# mySatellite.net
KiCad netlist of a schematic drawn in EAGLE
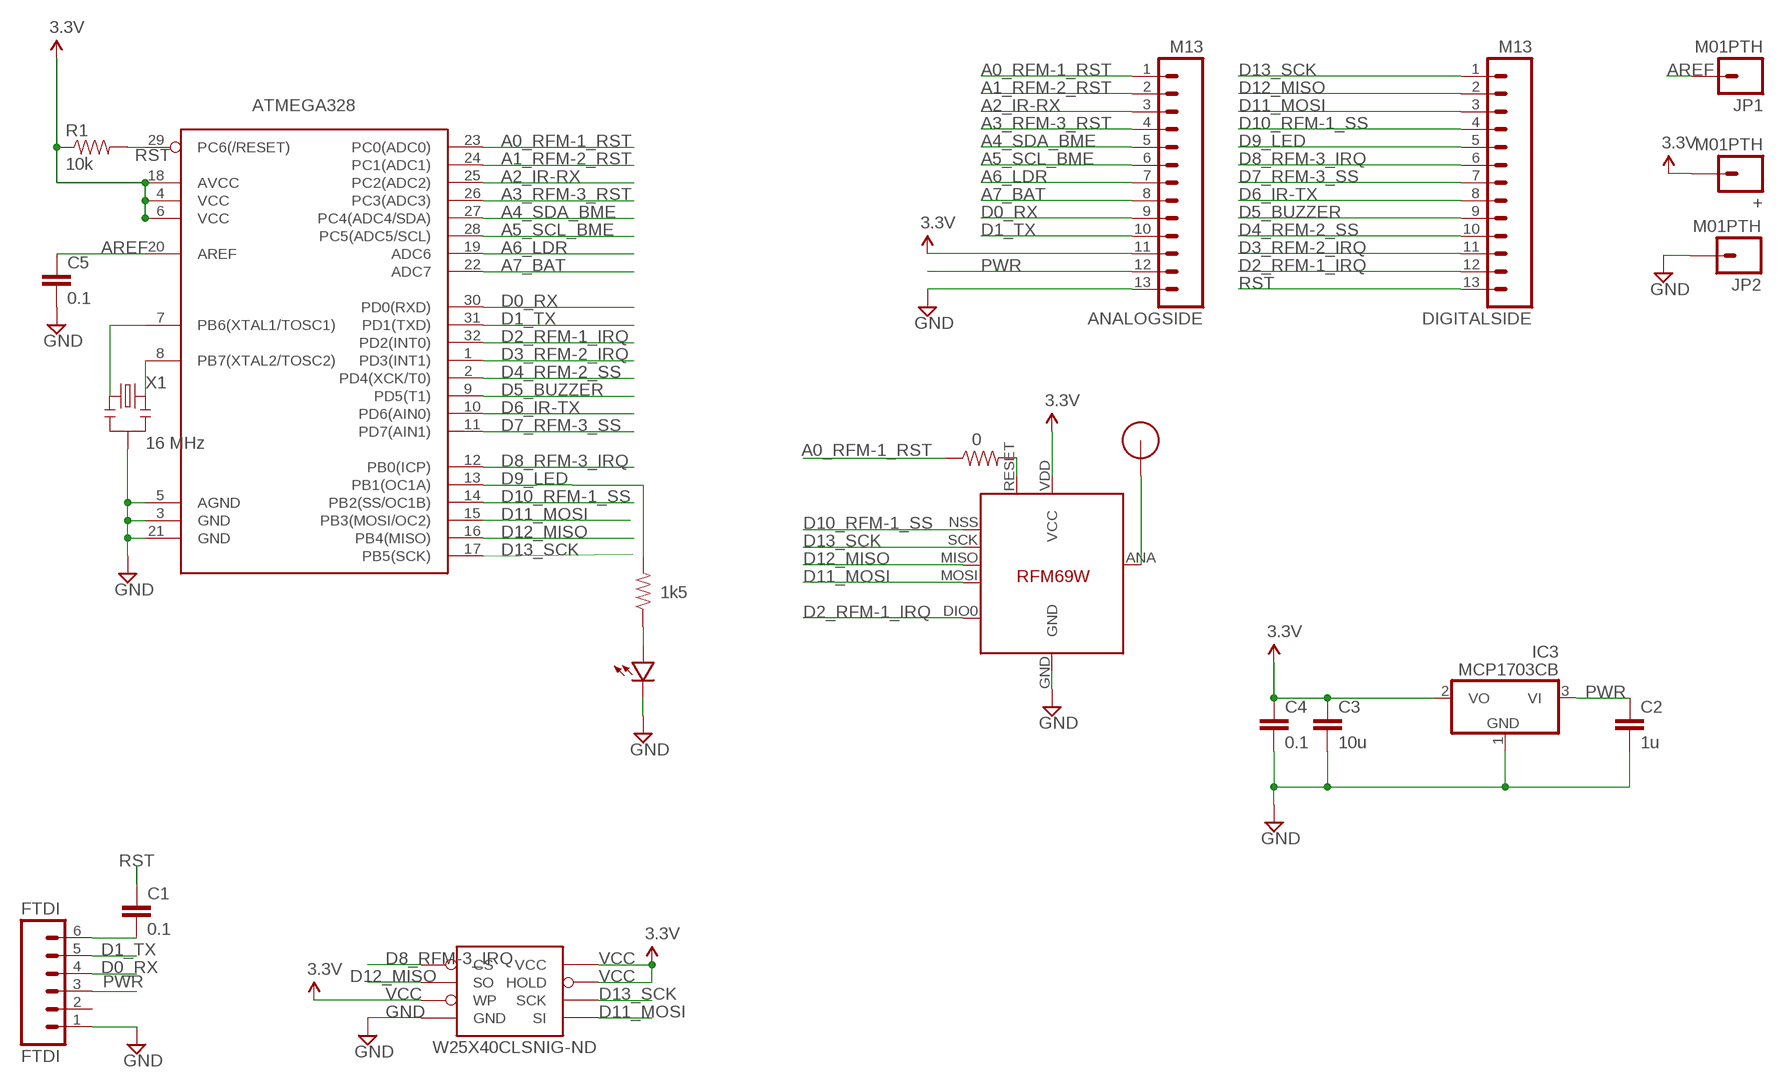
[diagram p0: schematic, sheet 1]

(export (version "E")
  (design (tool "Eeschema 10.0.6"))
  (components
    (comp (ref "+")
      (value "M01PTH")
      (footprint "eagle-import:1X01")
      (libsource (lib "eagle-import") (part "M01PTH"))
    )
    (comp (ref "ANALOGSIDE")
      (value "M13")
      (footprint "eagle-import:1X13")
      (libsource (lib "eagle-import") (part "M13"))
    )
    (comp (ref "ATMEGA328")
      (value "ATMega-328")
      (footprint "eagle-import:TQFP32-08")
      (libsource (lib "eagle-import") (part "ATMEGA168/328TQFP32"))
    )
    (comp (ref "C1")
      (value "0.1")
      (footprint "eagle-import:0603-CAP")
      (libsource (lib "eagle-import") (part "CAP0603-CAP"))
    )
    (comp (ref "C2")
      (value "1u")
      (footprint "eagle-import:0603-CAP")
      (libsource (lib "eagle-import") (part "CAP0603-CAP"))
    )
    (comp (ref "C3")
      (value "10u")
      (footprint "eagle-import:0805-CAP")
      (libsource (lib "eagle-import") (part "CAP0805-CAP"))
    )
    (comp (ref "C4")
      (value "0.1")
      (footprint "eagle-import:0603-CAP")
      (libsource (lib "eagle-import") (part "CAP0603-CAP"))
    )
    (comp (ref "C5")
      (value "0.1")
      (footprint "eagle-import:0603-CAP")
      (libsource (lib "eagle-import") (part "CAP0603-CAP"))
    )
    (comp (ref "DIGITALSIDE")
      (value "M13")
      (footprint "eagle-import:1X13")
      (libsource (lib "eagle-import") (part "M13"))
    )
    (comp (ref "FTDI")
      (value "FTDI")
      (footprint "eagle-import:1X06")
      (libsource (lib "eagle-import") (part "M06SIP"))
    )
    (comp (ref "IC3")
      (value "MCP1703CB")
      (footprint "eagle-import:SOT23")
      (libsource (lib "eagle-import") (part "MCP1703CB"))
    )
    (comp (ref "JP1")
      (value "M01PTH")
      (footprint "eagle-import:1X01")
      (libsource (lib "eagle-import") (part "M01PTH"))
    )
    (comp (ref "JP2")
      (value "M01PTH")
      (footprint "eagle-import:1X01")
      (libsource (lib "eagle-import") (part "M01PTH"))
    )
    (comp (ref "R1")
      (value "10k")
      (footprint "eagle-import:0603-RES")
      (libsource (lib "eagle-import") (part "RESISTOR0603-RES"))
    )
    (comp (ref "R2")
      (value "1k5")
      (footprint "eagle-import:0603-RES")
      (libsource (lib "eagle-import") (part "RESISTOR0603-RES"))
    )
    (comp (ref "R3")
      (value "0")
      (footprint "eagle-import:0603-RES")
      (libsource (lib "eagle-import") (part "RESISTOR0603-RES"))
    )
    (comp (ref "U$1")
      (value "RFM12B_ANTENNA")
      (footprint "eagle-import:RFM12B-ANTENNA")
      (libsource (lib "eagle-import") (part "RFM12B_ANTENNA"))
    )
    (comp (ref "U$2")
      (value "LED0603")
      (footprint "eagle-import:0603-LED")
      (libsource (lib "eagle-import") (part "LED0603"))
    )
    (comp (ref "U$5")
      (value "RFM69_MINIPADS")
      (footprint "eagle-import:RFM69W-MINPADS")
      (libsource (lib "eagle-import") (part "RFM69_MINIPADS"))
    )
    (comp (ref "W25X40CLSNIG-ND")
      (value "AT25F512BWIDE_5.3MM")
      (footprint "eagle-import:SO08WIDE")
      (libsource (lib "eagle-import") (part "AT25F512BWIDE_5.3MM"))
    )
    (comp (ref "X1")
      (value "16 MHz")
      (footprint "eagle-import:RESONATOR-SMD")
      (libsource (lib "eagle-import") (part "RESONATORSMD"))
    )
  )
  (nets
    (net (code "1") (name "/A0_RFM-1_RST") (class "Default")
      (node (ref "ANALOGSIDE") (pin "1") (pinfunction "1_1") (pintype "passive"))
      (node (ref "ATMEGA328") (pin "23") (pinfunction "PC0(ADC0)_23") (pintype "bidirectional"))
      (node (ref "R3") (pin "1") (pinfunction "1_1") (pintype "passive"))
    )
    (net (code "2") (name "/A1_RFM-2_RST") (class "Default")
      (node (ref "ANALOGSIDE") (pin "2") (pinfunction "2_2") (pintype "passive"))
      (node (ref "ATMEGA328") (pin "24") (pinfunction "PC1(ADC1)_24") (pintype "bidirectional"))
    )
    (net (code "3") (name "/A2_IR-RX") (class "Default")
      (node (ref "ANALOGSIDE") (pin "3") (pinfunction "3_3") (pintype "passive"))
      (node (ref "ATMEGA328") (pin "25") (pinfunction "PC2(ADC2)_25") (pintype "bidirectional"))
    )
    (net (code "4") (name "/A3_RFM-3_RST") (class "Default")
      (node (ref "ANALOGSIDE") (pin "4") (pinfunction "4_4") (pintype "passive"))
      (node (ref "ATMEGA328") (pin "26") (pinfunction "PC3(ADC3)_26") (pintype "bidirectional"))
    )
    (net (code "5") (name "/A4_SDA_BME") (class "Default")
      (node (ref "ANALOGSIDE") (pin "5") (pinfunction "5_5") (pintype "passive"))
      (node (ref "ATMEGA328") (pin "27") (pinfunction "PC4(ADC4/SDA)_27") (pintype "bidirectional"))
    )
    (net (code "6") (name "/A5_SCL_BME") (class "Default")
      (node (ref "ANALOGSIDE") (pin "6") (pinfunction "6_6") (pintype "passive"))
      (node (ref "ATMEGA328") (pin "28") (pinfunction "PC5(ADC5/SCL)_28") (pintype "bidirectional"))
    )
    (net (code "7") (name "/A6_LDR") (class "Default")
      (node (ref "ANALOGSIDE") (pin "7") (pinfunction "7_7") (pintype "passive"))
      (node (ref "ATMEGA328") (pin "19") (pinfunction "ADC6_19") (pintype "bidirectional"))
    )
    (net (code "8") (name "/A7_BAT") (class "Default")
      (node (ref "ANALOGSIDE") (pin "8") (pinfunction "8_8") (pintype "passive"))
      (node (ref "ATMEGA328") (pin "22") (pinfunction "ADC7_22") (pintype "bidirectional"))
    )
    (net (code "9") (name "/AREF") (class "Default")
      (node (ref "ATMEGA328") (pin "20") (pinfunction "AREF_20") (pintype "bidirectional"))
      (node (ref "C5") (pin "1") (pinfunction "1_1") (pintype "passive"))
      (node (ref "JP1") (pin "1") (pinfunction "1_1") (pintype "passive"))
    )
    (net (code "10") (name "/D0_RX") (class "Default")
      (node (ref "ANALOGSIDE") (pin "9") (pinfunction "9_9") (pintype "passive"))
      (node (ref "ATMEGA328") (pin "30") (pinfunction "PD0(RXD)_30") (pintype "bidirectional"))
      (node (ref "FTDI") (pin "4") (pinfunction "4_4") (pintype "passive"))
    )
    (net (code "11") (name "/D1_TX") (class "Default")
      (node (ref "ANALOGSIDE") (pin "10") (pinfunction "10_10") (pintype "passive"))
      (node (ref "ATMEGA328") (pin "31") (pinfunction "PD1(TXD)_31") (pintype "bidirectional"))
      (node (ref "FTDI") (pin "5") (pinfunction "5_5") (pintype "passive"))
    )
    (net (code "12") (name "/D2_RFM-1_IRQ") (class "Default")
      (node (ref "ATMEGA328") (pin "32") (pinfunction "PD2(INT0)_32") (pintype "bidirectional"))
      (node (ref "DIGITALSIDE") (pin "12") (pinfunction "12_12") (pintype "passive"))
      (node (ref "U$5") (pin "DIO0") (pinfunction "DIO0/IRQ_DIO0") (pintype "open_collector"))
    )
    (net (code "13") (name "/D3_RFM-2_IRQ") (class "Default")
      (node (ref "ATMEGA328") (pin "1") (pinfunction "PD3(INT1)_1") (pintype "bidirectional"))
      (node (ref "DIGITALSIDE") (pin "11") (pinfunction "11_11") (pintype "passive"))
    )
    (net (code "14") (name "/D4_RFM-2_SS") (class "Default")
      (node (ref "ATMEGA328") (pin "2") (pinfunction "PD4(XCK/T0)_2") (pintype "bidirectional"))
      (node (ref "DIGITALSIDE") (pin "10") (pinfunction "10_10") (pintype "passive"))
    )
    (net (code "15") (name "/D5_BUZZER") (class "Default")
      (node (ref "ATMEGA328") (pin "9") (pinfunction "PD5(T1)_9") (pintype "bidirectional"))
      (node (ref "DIGITALSIDE") (pin "9") (pinfunction "9_9") (pintype "passive"))
    )
    (net (code "16") (name "/D6_IR-TX") (class "Default")
      (node (ref "ATMEGA328") (pin "10") (pinfunction "PD6(AIN0)_10") (pintype "bidirectional"))
      (node (ref "DIGITALSIDE") (pin "8") (pinfunction "8_8") (pintype "passive"))
    )
    (net (code "17") (name "/D7_RFM-3_SS") (class "Default")
      (node (ref "ATMEGA328") (pin "11") (pinfunction "PD7(AIN1)_11") (pintype "bidirectional"))
      (node (ref "DIGITALSIDE") (pin "7") (pinfunction "7_7") (pintype "passive"))
    )
    (net (code "18") (name "/D8_RFM-3_IRQ") (class "Default")
      (node (ref "ATMEGA328") (pin "12") (pinfunction "PB0(ICP)_12") (pintype "bidirectional"))
      (node (ref "DIGITALSIDE") (pin "6") (pinfunction "6_6") (pintype "passive"))
      (node (ref "W25X40CLSNIG-ND") (pin "1") (pinfunction "CS_1") (pintype "bidirectional"))
    )
    (net (code "19") (name "/D9_LED") (class "Default")
      (node (ref "ATMEGA328") (pin "13") (pinfunction "PB1(OC1A)_13") (pintype "bidirectional"))
      (node (ref "DIGITALSIDE") (pin "5") (pinfunction "5_5") (pintype "passive"))
      (node (ref "R2") (pin "2") (pinfunction "2_2") (pintype "passive"))
    )
    (net (code "20") (name "/D10_RFM-1_SS") (class "Default")
      (node (ref "ATMEGA328") (pin "14") (pinfunction "PB2(SS/OC1B)_14") (pintype "bidirectional"))
      (node (ref "DIGITALSIDE") (pin "4") (pinfunction "4_4") (pintype "passive"))
      (node (ref "U$5") (pin "NSS") (pinfunction "SEL_NSS") (pintype "input"))
    )
    (net (code "21") (name "/D11_MOSI") (class "Default")
      (node (ref "ATMEGA328") (pin "15") (pinfunction "PB3(MOSI/OC2)_15") (pintype "bidirectional"))
      (node (ref "DIGITALSIDE") (pin "3") (pinfunction "3_3") (pintype "passive"))
      (node (ref "U$5") (pin "MOSI") (pinfunction "MOSI_MOSI") (pintype "output"))
      (node (ref "W25X40CLSNIG-ND") (pin "5") (pinfunction "SI_5") (pintype "bidirectional"))
    )
    (net (code "22") (name "/D12_MISO") (class "Default")
      (node (ref "ATMEGA328") (pin "16") (pinfunction "PB4(MISO)_16") (pintype "bidirectional"))
      (node (ref "DIGITALSIDE") (pin "2") (pinfunction "2_2") (pintype "passive"))
      (node (ref "U$5") (pin "MISO") (pinfunction "MISO_MISO") (pintype "input"))
      (node (ref "W25X40CLSNIG-ND") (pin "2") (pinfunction "SO_2") (pintype "bidirectional"))
    )
    (net (code "23") (name "/D13_SCK") (class "Default")
      (node (ref "ATMEGA328") (pin "17") (pinfunction "PB5(SCK)_17") (pintype "bidirectional"))
      (node (ref "DIGITALSIDE") (pin "1") (pinfunction "1_1") (pintype "passive"))
      (node (ref "U$5") (pin "SCK") (pinfunction "SCK_SCK") (pintype "input"))
      (node (ref "W25X40CLSNIG-ND") (pin "6") (pinfunction "SCK_6") (pintype "bidirectional"))
    )
    (net (code "24") (name "/PWR") (class "Default")
      (node (ref "ANALOGSIDE") (pin "12") (pinfunction "12_12") (pintype "passive"))
      (node (ref "C2") (pin "1") (pinfunction "1_1") (pintype "passive"))
      (node (ref "FTDI") (pin "3") (pinfunction "3_3") (pintype "passive"))
      (node (ref "IC3") (pin "3") (pinfunction "VI_3") (pintype "input"))
    )
    (net (code "25") (name "/RST") (class "Default")
      (node (ref "ATMEGA328") (pin "29") (pinfunction "PC6(/RESET)_29") (pintype "bidirectional"))
      (node (ref "C1") (pin "1") (pinfunction "1_1") (pintype "passive"))
      (node (ref "DIGITALSIDE") (pin "13") (pinfunction "13_13") (pintype "passive"))
      (node (ref "R1") (pin "2") (pinfunction "2_2") (pintype "passive"))
    )
    (net (code "26") (name "3.3V") (class "Default")
      (node (ref "+") (pin "1") (pinfunction "1_1") (pintype "passive"))
      (node (ref "ANALOGSIDE") (pin "11") (pinfunction "11_11") (pintype "passive"))
      (node (ref "ATMEGA328") (pin "18") (pinfunction "AVCC_18") (pintype "bidirectional"))
      (node (ref "ATMEGA328") (pin "4") (pinfunction "VCC_4") (pintype "bidirectional"))
      (node (ref "ATMEGA328") (pin "6") (pinfunction "VCC_6") (pintype "bidirectional"))
      (node (ref "C3") (pin "1") (pinfunction "1_1") (pintype "passive"))
      (node (ref "C4") (pin "1") (pinfunction "1_1") (pintype "passive"))
      (node (ref "IC3") (pin "2") (pinfunction "VO_2") (pintype "passive"))
      (node (ref "R1") (pin "1") (pinfunction "1_1") (pintype "passive"))
      (node (ref "U$5") (pin "VDD") (pinfunction "VCC_VDD") (pintype "power_in"))
      (node (ref "W25X40CLSNIG-ND") (pin "3") (pinfunction "WP_3") (pintype "bidirectional"))
      (node (ref "W25X40CLSNIG-ND") (pin "7") (pinfunction "HOLD_7") (pintype "bidirectional"))
      (node (ref "W25X40CLSNIG-ND") (pin "8") (pinfunction "VCC_8") (pintype "bidirectional"))
    )
    (net (code "27") (name "GND") (class "Default")
      (node (ref "ANALOGSIDE") (pin "13") (pinfunction "13_13") (pintype "passive"))
      (node (ref "ATMEGA328") (pin "21") (pinfunction "GND_21") (pintype "bidirectional"))
      (node (ref "ATMEGA328") (pin "3") (pinfunction "GND_3") (pintype "bidirectional"))
      (node (ref "ATMEGA328") (pin "5") (pinfunction "AGND_5") (pintype "bidirectional"))
      (node (ref "C2") (pin "2") (pinfunction "2_2") (pintype "passive"))
      (node (ref "C3") (pin "2") (pinfunction "2_2") (pintype "passive"))
      (node (ref "C4") (pin "2") (pinfunction "2_2") (pintype "passive"))
      (node (ref "C5") (pin "2") (pinfunction "2_2") (pintype "passive"))
      (node (ref "FTDI") (pin "1") (pinfunction "1_1") (pintype "passive"))
      (node (ref "IC3") (pin "1") (pinfunction "GND_1") (pintype "passive"))
      (node (ref "JP2") (pin "1") (pinfunction "1_1") (pintype "passive"))
      (node (ref "U$2") (pin "MINUS") (pinfunction "MINUS_MINUS") (pintype "passive"))
      (node (ref "U$5") (pin "GND") (pinfunction "GND_GND") (pintype "power_in"))
      (node (ref "W25X40CLSNIG-ND") (pin "4") (pinfunction "GND_4") (pintype "bidirectional"))
      (node (ref "X1") (pin "2") (pinfunction "2_2") (pintype "passive"))
    )
    (net (code "28") (name "Net-(ATMEGA328-PB6(XTAL1{slash}TOSC1))") (class "Default")
      (node (ref "ATMEGA328") (pin "7") (pinfunction "PB6(XTAL1/TOSC1)_7") (pintype "bidirectional"))
      (node (ref "X1") (pin "1") (pinfunction "1_1") (pintype "passive"))
    )
    (net (code "29") (name "Net-(ATMEGA328-PB7(XTAL2{slash}TOSC2))") (class "Default")
      (node (ref "ATMEGA328") (pin "8") (pinfunction "PB7(XTAL2/TOSC2)_8") (pintype "bidirectional"))
      (node (ref "X1") (pin "3") (pinfunction "3_3") (pintype "passive"))
    )
    (net (code "30") (name "Net-(C1-Pad2)") (class "Default")
      (node (ref "C1") (pin "2") (pinfunction "2_2") (pintype "passive"))
      (node (ref "FTDI") (pin "6") (pinfunction "6_6") (pintype "passive"))
    )
    (net (code "31") (name "Net-(R2-Pad1)") (class "Default")
      (node (ref "R2") (pin "1") (pinfunction "1_1") (pintype "passive"))
      (node (ref "U$2") (pin "PLUS") (pinfunction "PLUS_PLUS") (pintype "passive"))
    )
    (net (code "32") (name "Net-(R3-Pad2)") (class "Default")
      (node (ref "R3") (pin "2") (pinfunction "2_2") (pintype "passive"))
      (node (ref "U$5") (pin "RESET") (pinfunction "RESET_RESET") (pintype "input"))
    )
    (net (code "33") (name "Net-(U$1-1)") (class "Default")
      (node (ref "U$1") (pin "P$1") (pinfunction "1_P$1") (pintype "bidirectional"))
      (node (ref "U$5") (pin "ANA") (pinfunction "ANT_ANA") (pintype "passive"))
    )
    (net (code "34") (name "unconnected-(FTDI-Pad2)") (class "Default")
      (node (ref "FTDI") (pin "2") (pinfunction "2_2") (pintype "passive"))
    )
  )
)
